# SCH_LoRaRice_Gateway__2024-05-29.net
KiCad netlist of a schematic drawn in EasyEDA
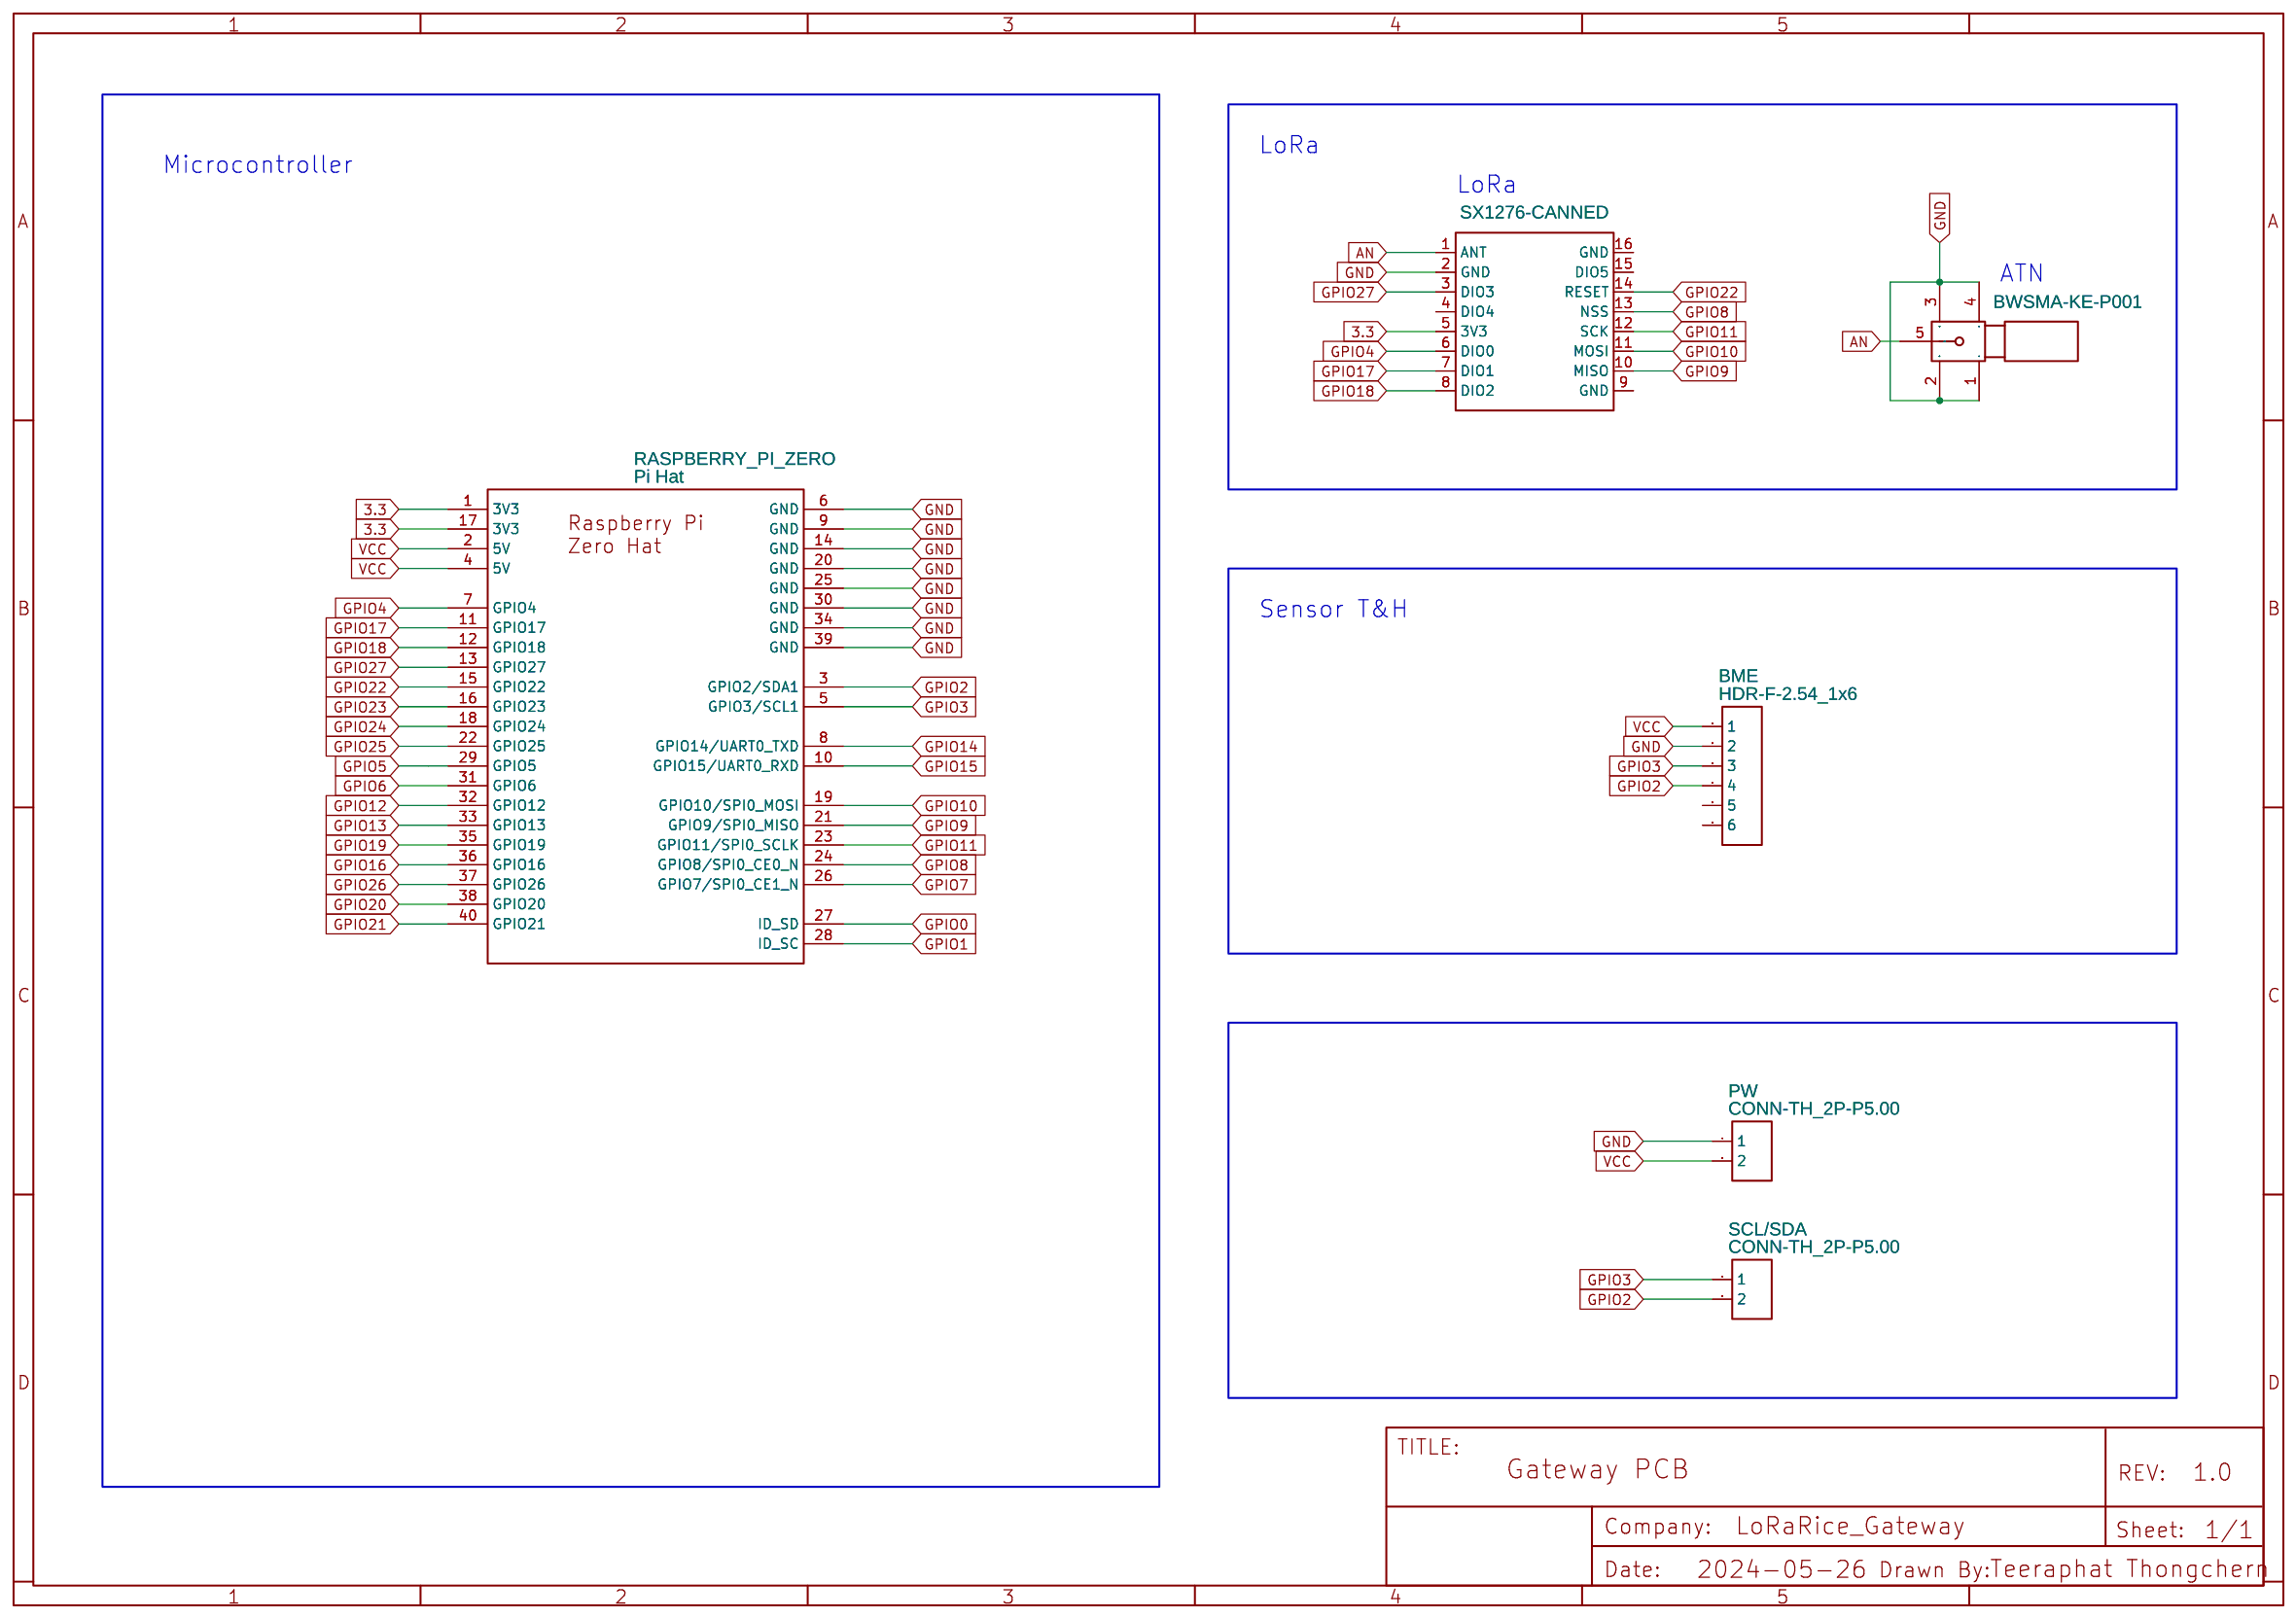
[diagram p0: schematic sheet]

(export (version "E")
  (design (tool "Eeschema 10.0.6"))
  (components
    (comp (ref "ATN")
      (value "BWSMA-KE-P001")
      (fields (field (name "Manufacturer") "BAT WIRELESS(蝙蝠无线)"))
      (libsource (lib "") (part "BWSMA-KE-P001"))
    )
    (comp (ref "BME") (value "HDR-F-2.54_1x6") (libsource (lib "") (part "HDR-F-2.54_1x6")))
    (comp (ref "LORA")
      (value "SX1276-CANNED")
      (fields (field (name "Manufacturer Part") "LoRa1276-C1") (field (name "Manufacturer") "G-NiceRF"))
      (libsource (lib "") (part "SX1276-CANNED"))
    )
    (comp (ref "PW") (value "CONN-TH_2P-P5.00") (libsource (lib "") (part "CONN-TH_2P-P5.00")))
    (comp (ref "RASPBERRY_PI_ZERO")
      (value "Pi Hat")
      (fields (field (name "Manufacturer") "Raspberry Pi Foundation"))
      (libsource (lib "") (part "RPI ZERO 2W"))
    )
    (comp (ref "SCL/SDA") (value "CONN-TH_2P-P5.00") (libsource (lib "") (part "CONN-TH_2P-P5.00_1")))
  )
  (nets
    (net (code "1") (name "3.3") (class "Default")
      (node (ref "LORA") (pin "5") (pinfunction "3V3_5") (pintype "unspecified"))
      (node (ref "RASPBERRY_PI_ZERO") (pin "1") (pinfunction "3V3_1") (pintype "unspecified"))
      (node (ref "RASPBERRY_PI_ZERO") (pin "17") (pinfunction "3V3_17") (pintype "unspecified"))
    )
    (net (code "2") (name "AN") (class "Default")
      (node (ref "ATN") (pin "5") (pinfunction "5_5") (pintype "unspecified"))
      (node (ref "LORA") (pin "1") (pinfunction "ANT_1") (pintype "unspecified"))
    )
    (net (code "3") (name "GND") (class "Default")
      (node (ref "ATN") (pin "1") (pinfunction "1_1") (pintype "unspecified"))
      (node (ref "ATN") (pin "2") (pinfunction "2_2") (pintype "unspecified"))
      (node (ref "ATN") (pin "3") (pinfunction "3_3") (pintype "unspecified"))
      (node (ref "ATN") (pin "4") (pinfunction "4_4") (pintype "unspecified"))
      (node (ref "BME") (pin "2") (pinfunction "2_2") (pintype "input"))
      (node (ref "LORA") (pin "2") (pinfunction "GND_2") (pintype "unspecified"))
      (node (ref "PW") (pin "1") (pinfunction "1_1") (pintype "unspecified"))
      (node (ref "RASPBERRY_PI_ZERO") (pin "14") (pinfunction "GND_14") (pintype "unspecified"))
      (node (ref "RASPBERRY_PI_ZERO") (pin "20") (pinfunction "GND_20") (pintype "unspecified"))
      (node (ref "RASPBERRY_PI_ZERO") (pin "25") (pinfunction "GND_25") (pintype "unspecified"))
      (node (ref "RASPBERRY_PI_ZERO") (pin "30") (pinfunction "GND_30") (pintype "unspecified"))
      (node (ref "RASPBERRY_PI_ZERO") (pin "34") (pinfunction "GND_34") (pintype "unspecified"))
      (node (ref "RASPBERRY_PI_ZERO") (pin "39") (pinfunction "GND_39") (pintype "unspecified"))
      (node (ref "RASPBERRY_PI_ZERO") (pin "6") (pinfunction "GND_6") (pintype "unspecified"))
      (node (ref "RASPBERRY_PI_ZERO") (pin "9") (pinfunction "GND_9") (pintype "unspecified"))
    )
    (net (code "4") (name "GPIO0") (class "Default")
      (node (ref "RASPBERRY_PI_ZERO") (pin "27") (pinfunction "ID_SD_27") (pintype "unspecified"))
    )
    (net (code "5") (name "GPIO1") (class "Default")
      (node (ref "RASPBERRY_PI_ZERO") (pin "28") (pinfunction "ID_SC_28") (pintype "unspecified"))
    )
    (net (code "6") (name "GPIO2") (class "Default")
      (node (ref "BME") (pin "4") (pinfunction "4_4") (pintype "input"))
      (node (ref "RASPBERRY_PI_ZERO") (pin "3") (pinfunction "GPIO2/SDA1_3") (pintype "unspecified"))
      (node (ref "SCL/SDA") (pin "2") (pinfunction "2_2") (pintype "unspecified"))
    )
    (net (code "7") (name "GPIO3") (class "Default")
      (node (ref "BME") (pin "3") (pinfunction "3_3") (pintype "input"))
      (node (ref "RASPBERRY_PI_ZERO") (pin "5") (pinfunction "GPIO3/SCL1_5") (pintype "unspecified"))
      (node (ref "SCL/SDA") (pin "1") (pinfunction "1_1") (pintype "unspecified"))
    )
    (net (code "8") (name "GPIO4") (class "Default")
      (node (ref "LORA") (pin "6") (pinfunction "DIO0_6") (pintype "unspecified"))
      (node (ref "RASPBERRY_PI_ZERO") (pin "7") (pinfunction "GPIO4_7") (pintype "unspecified"))
    )
    (net (code "9") (name "GPIO5") (class "Default")
      (node (ref "RASPBERRY_PI_ZERO") (pin "29") (pinfunction "GPIO5_29") (pintype "unspecified"))
    )
    (net (code "10") (name "GPIO6") (class "Default")
      (node (ref "RASPBERRY_PI_ZERO") (pin "31") (pinfunction "GPIO6_31") (pintype "unspecified"))
    )
    (net (code "11") (name "GPIO7") (class "Default")
      (node (ref "RASPBERRY_PI_ZERO") (pin "26") (pinfunction "GPIO7/SPI0_CE1_N_26") (pintype "unspecified"))
    )
    (net (code "12") (name "GPIO8") (class "Default")
      (node (ref "LORA") (pin "13") (pinfunction "NSS_13") (pintype "unspecified"))
      (node (ref "RASPBERRY_PI_ZERO") (pin "24") (pinfunction "GPIO8/SPI0_CE0_N_24") (pintype "unspecified"))
    )
    (net (code "13") (name "GPIO9") (class "Default")
      (node (ref "LORA") (pin "10") (pinfunction "MISO_10") (pintype "unspecified"))
      (node (ref "RASPBERRY_PI_ZERO") (pin "21") (pinfunction "GPIO9/SPI0_MISO_21") (pintype "unspecified"))
    )
    (net (code "14") (name "GPIO10") (class "Default")
      (node (ref "LORA") (pin "11") (pinfunction "MOSI_11") (pintype "unspecified"))
      (node (ref "RASPBERRY_PI_ZERO") (pin "19") (pinfunction "GPIO10/SPI0_MOSI_19") (pintype "unspecified"))
    )
    (net (code "15") (name "GPIO11") (class "Default")
      (node (ref "LORA") (pin "12") (pinfunction "SCK_12") (pintype "unspecified"))
      (node (ref "RASPBERRY_PI_ZERO") (pin "23") (pinfunction "GPIO11/SPI0_SCLK_23") (pintype "unspecified"))
    )
    (net (code "16") (name "GPIO12") (class "Default")
      (node (ref "RASPBERRY_PI_ZERO") (pin "32") (pinfunction "GPIO12_32") (pintype "unspecified"))
    )
    (net (code "17") (name "GPIO13") (class "Default")
      (node (ref "RASPBERRY_PI_ZERO") (pin "33") (pinfunction "GPIO13_33") (pintype "unspecified"))
    )
    (net (code "18") (name "GPIO14") (class "Default")
      (node (ref "RASPBERRY_PI_ZERO") (pin "8") (pinfunction "GPIO14/UART0_TXD_8") (pintype "unspecified"))
    )
    (net (code "19") (name "GPIO15") (class "Default")
      (node (ref "RASPBERRY_PI_ZERO") (pin "10") (pinfunction "GPIO15/UART0_RXD_10") (pintype "unspecified"))
    )
    (net (code "20") (name "GPIO16") (class "Default")
      (node (ref "RASPBERRY_PI_ZERO") (pin "36") (pinfunction "GPIO16_36") (pintype "unspecified"))
    )
    (net (code "21") (name "GPIO17") (class "Default")
      (node (ref "LORA") (pin "7") (pinfunction "DIO1_7") (pintype "unspecified"))
      (node (ref "RASPBERRY_PI_ZERO") (pin "11") (pinfunction "GPIO17_11") (pintype "unspecified"))
    )
    (net (code "22") (name "GPIO18") (class "Default")
      (node (ref "LORA") (pin "8") (pinfunction "DIO2_8") (pintype "unspecified"))
      (node (ref "RASPBERRY_PI_ZERO") (pin "12") (pinfunction "GPIO18_12") (pintype "unspecified"))
    )
    (net (code "23") (name "GPIO19") (class "Default")
      (node (ref "RASPBERRY_PI_ZERO") (pin "35") (pinfunction "GPIO19_35") (pintype "unspecified"))
    )
    (net (code "24") (name "GPIO20") (class "Default")
      (node (ref "RASPBERRY_PI_ZERO") (pin "38") (pinfunction "GPIO20_38") (pintype "unspecified"))
    )
    (net (code "25") (name "GPIO21") (class "Default")
      (node (ref "RASPBERRY_PI_ZERO") (pin "40") (pinfunction "GPIO21_40") (pintype "unspecified"))
    )
    (net (code "26") (name "GPIO22") (class "Default")
      (node (ref "LORA") (pin "14") (pinfunction "RESET_14") (pintype "unspecified"))
      (node (ref "RASPBERRY_PI_ZERO") (pin "15") (pinfunction "GPIO22_15") (pintype "unspecified"))
    )
    (net (code "27") (name "GPIO23") (class "Default")
      (node (ref "RASPBERRY_PI_ZERO") (pin "16") (pinfunction "GPIO23_16") (pintype "unspecified"))
    )
    (net (code "28") (name "GPIO24") (class "Default")
      (node (ref "RASPBERRY_PI_ZERO") (pin "18") (pinfunction "GPIO24_18") (pintype "unspecified"))
    )
    (net (code "29") (name "GPIO25") (class "Default")
      (node (ref "RASPBERRY_PI_ZERO") (pin "22") (pinfunction "GPIO25_22") (pintype "unspecified"))
    )
    (net (code "30") (name "GPIO26") (class "Default")
      (node (ref "RASPBERRY_PI_ZERO") (pin "37") (pinfunction "GPIO26_37") (pintype "unspecified"))
    )
    (net (code "31") (name "GPIO27") (class "Default")
      (node (ref "LORA") (pin "3") (pinfunction "DIO3_3") (pintype "unspecified"))
      (node (ref "RASPBERRY_PI_ZERO") (pin "13") (pinfunction "GPIO27_13") (pintype "unspecified"))
    )
    (net (code "32") (name "VCC") (class "Default")
      (node (ref "BME") (pin "1") (pinfunction "1_1") (pintype "input"))
      (node (ref "PW") (pin "2") (pinfunction "2_2") (pintype "unspecified"))
      (node (ref "RASPBERRY_PI_ZERO") (pin "2") (pinfunction "5V_2") (pintype "unspecified"))
      (node (ref "RASPBERRY_PI_ZERO") (pin "4") (pinfunction "5V_4") (pintype "unspecified"))
    )
    (net (code "33") (name "unconnected-(BME-Pad5)") (class "Default")
      (node (ref "BME") (pin "5") (pinfunction "5_5") (pintype "input"))
    )
    (net (code "34") (name "unconnected-(BME-Pad6)") (class "Default")
      (node (ref "BME") (pin "6") (pinfunction "6_6") (pintype "input"))
    )
    (net (code "35") (name "unconnected-(LORA-DIO4-Pad4)") (class "Default")
      (node (ref "LORA") (pin "4") (pinfunction "DIO4_4") (pintype "unspecified"))
    )
    (net (code "36") (name "unconnected-(LORA-DIO5-Pad15)") (class "Default")
      (node (ref "LORA") (pin "15") (pinfunction "DIO5_15") (pintype "unspecified"))
    )
    (net (code "37") (name "unconnected-(LORA-GND-Pad9)") (class "Default")
      (node (ref "LORA") (pin "9") (pinfunction "GND_9") (pintype "unspecified"))
    )
    (net (code "38") (name "unconnected-(LORA-GND-Pad16)") (class "Default")
      (node (ref "LORA") (pin "16") (pinfunction "GND_16") (pintype "unspecified"))
    )
  )
)
